# Status_Board.net
KiCad netlist of a schematic drawn in EAGLE
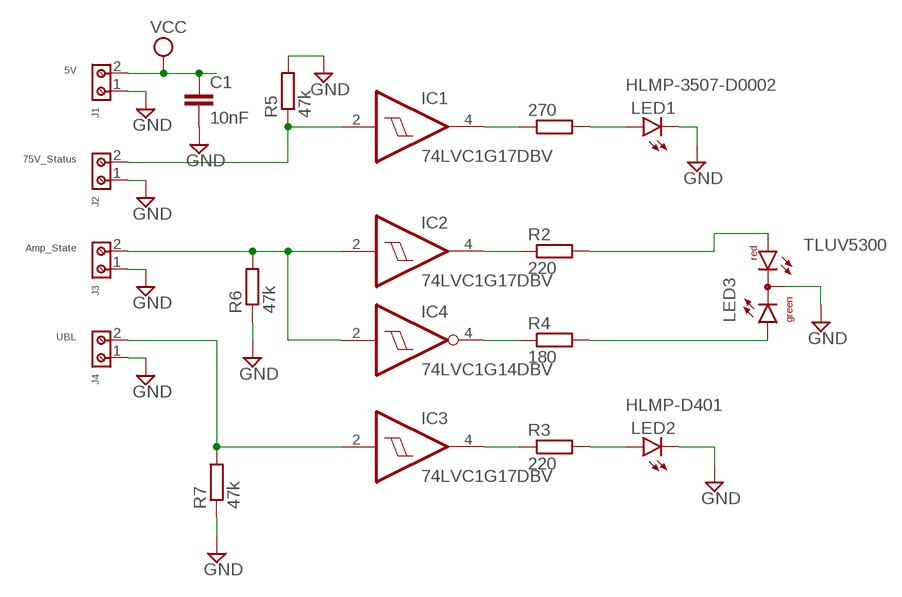
[diagram p0: schematic, sheet 1]

(export (version "E")
  (design (tool "Eeschema 10.0.6"))
  (components
    (comp (ref "270")
      (value "R-EU_R0805")
      (footprint "eagle-import:R0805")
      (libsource (lib "eagle-import") (part "R-EU_R0805"))
    )
    (comp (ref "C1")
      (value "10nF")
      (footprint "eagle-import:C0805")
      (libsource (lib "eagle-import") (part "C-EUC0805"))
    )
    (comp (ref "IC1")
      (value "74LVC1G17DBV")
      (footprint "eagle-import:SOT23-5")
      (libsource (lib "eagle-import") (part "741G17DBVLVC"))
    )
    (comp (ref "IC2")
      (value "74LVC1G17DBV")
      (footprint "eagle-import:SOT23-5")
      (libsource (lib "eagle-import") (part "741G17DBVLVC"))
    )
    (comp (ref "IC3")
      (value "74LVC1G17DBV")
      (footprint "eagle-import:SOT23-5")
      (libsource (lib "eagle-import") (part "741G17DBVLVC"))
    )
    (comp (ref "IC4")
      (value "74LVC1G14DBV")
      (footprint "eagle-import:SOT23-5")
      (libsource (lib "eagle-import") (part "741G14DBVLVC"))
    )
    (comp (ref "J1")
      (value "5V")
      (footprint "eagle-import:691210910002")
      (libsource (lib "eagle-import") (part "691210910002"))
    )
    (comp (ref "J2")
      (value "75V_Status")
      (footprint "eagle-import:691210910002")
      (libsource (lib "eagle-import") (part "691210910002"))
    )
    (comp (ref "J3")
      (value "Amp_State")
      (footprint "eagle-import:691210910002")
      (libsource (lib "eagle-import") (part "691210910002"))
    )
    (comp (ref "J4")
      (value "UBL")
      (footprint "eagle-import:691210910002")
      (libsource (lib "eagle-import") (part "691210910002"))
    )
    (comp (ref "LED1")
      (value "LED5MM")
      (footprint "eagle-import:LED5MM")
      (libsource (lib "eagle-import") (part "LED5MM"))
    )
    (comp (ref "LED2")
      (value "LED5MM")
      (footprint "eagle-import:LED5MM")
      (libsource (lib "eagle-import") (part "LED5MM"))
    )
    (comp (ref "LED3")
      (value "DUOLED-RG-C")
      (footprint "eagle-import:DUOLED-C-5MM")
      (libsource (lib "eagle-import") (part "DUOLED-RG-C"))
    )
    (comp (ref "R2")
      (value "220")
      (footprint "eagle-import:R0805")
      (libsource (lib "eagle-import") (part "R-EU_R0805"))
    )
    (comp (ref "R3")
      (value "220")
      (footprint "eagle-import:R0805")
      (libsource (lib "eagle-import") (part "R-EU_R0805"))
    )
    (comp (ref "R4")
      (value "180")
      (footprint "eagle-import:R0805")
      (libsource (lib "eagle-import") (part "R-EU_R0805"))
    )
    (comp (ref "R5")
      (value "47k")
      (footprint "eagle-import:R0805")
      (libsource (lib "eagle-import") (part "R-EU_R0805"))
    )
    (comp (ref "R6")
      (value "47k")
      (footprint "eagle-import:R0805")
      (libsource (lib "eagle-import") (part "R-EU_R0805"))
    )
    (comp (ref "R7")
      (value "47k")
      (footprint "eagle-import:R0805")
      (libsource (lib "eagle-import") (part "R-EU_R0805"))
    )
  )
  (nets
    (net (code "1") (name "GND") (class "Default")
      (node (ref "C1") (pin "2") (pinfunction "2_2") (pintype "passive"))
      (node (ref "J1") (pin "1") (pinfunction "1_1") (pintype "passive"))
      (node (ref "J2") (pin "1") (pinfunction "1_1") (pintype "passive"))
      (node (ref "J3") (pin "1") (pinfunction "1_1") (pintype "passive"))
      (node (ref "J4") (pin "1") (pinfunction "1_1") (pintype "passive"))
      (node (ref "LED1") (pin "K") (pinfunction "C_K") (pintype "passive"))
      (node (ref "LED2") (pin "K") (pinfunction "C_K") (pintype "passive"))
      (node (ref "LED3") (pin "C") (pinfunction "C_C") (pintype "passive"))
      (node (ref "R5") (pin "2") (pinfunction "2_2") (pintype "passive"))
      (node (ref "R6") (pin "1") (pinfunction "1_1") (pintype "passive"))
      (node (ref "R7") (pin "1") (pinfunction "1_1") (pintype "passive"))
    )
    (net (code "2") (name "Net-(270-Pad2)") (class "Default")
      (node (ref "270") (pin "2") (pinfunction "2_2") (pintype "passive"))
      (node (ref "LED1") (pin "A") (pinfunction "A_A") (pintype "passive"))
    )
    (net (code "3") (name "Net-(IC1A-I)") (class "Default")
      (node (ref "IC1") (pin "2") (pinfunction "I_2") (pintype "input"))
      (node (ref "J2") (pin "2") (pinfunction "2_2") (pintype "passive"))
      (node (ref "R5") (pin "1") (pinfunction "1_1") (pintype "passive"))
    )
    (net (code "4") (name "Net-(IC1A-O)") (class "Default")
      (node (ref "270") (pin "1") (pinfunction "1_1") (pintype "passive"))
      (node (ref "IC1") (pin "4") (pinfunction "O_4") (pintype "output"))
    )
    (net (code "5") (name "Net-(IC2A-I)") (class "Default")
      (node (ref "IC2") (pin "2") (pinfunction "I_2") (pintype "input"))
      (node (ref "IC4") (pin "2") (pinfunction "I_2") (pintype "input"))
      (node (ref "J3") (pin "2") (pinfunction "2_2") (pintype "passive"))
      (node (ref "R6") (pin "2") (pinfunction "2_2") (pintype "passive"))
    )
    (net (code "6") (name "Net-(IC2A-O)") (class "Default")
      (node (ref "IC2") (pin "4") (pinfunction "O_4") (pintype "output"))
      (node (ref "R2") (pin "1") (pinfunction "1_1") (pintype "passive"))
    )
    (net (code "7") (name "Net-(IC3A-I)") (class "Default")
      (node (ref "IC3") (pin "2") (pinfunction "I_2") (pintype "input"))
      (node (ref "J4") (pin "2") (pinfunction "2_2") (pintype "passive"))
      (node (ref "R7") (pin "2") (pinfunction "2_2") (pintype "passive"))
    )
    (net (code "8") (name "Net-(IC3A-O)") (class "Default")
      (node (ref "IC3") (pin "4") (pinfunction "O_4") (pintype "output"))
      (node (ref "R3") (pin "1") (pinfunction "1_1") (pintype "passive"))
    )
    (net (code "9") (name "Net-(IC4A-O)") (class "Default")
      (node (ref "IC4") (pin "4") (pinfunction "O_4") (pintype "output"))
      (node (ref "R4") (pin "1") (pinfunction "1_1") (pintype "passive"))
    )
    (net (code "10") (name "Net-(LED2-PadA)") (class "Default")
      (node (ref "LED2") (pin "A") (pinfunction "A_A") (pintype "passive"))
      (node (ref "R3") (pin "2") (pinfunction "2_2") (pintype "passive"))
    )
    (net (code "11") (name "Net-(LED3-AG)") (class "Default")
      (node (ref "LED3") (pin "AX") (pinfunction "AG_AX") (pintype "passive"))
      (node (ref "R4") (pin "2") (pinfunction "2_2") (pintype "passive"))
    )
    (net (code "12") (name "Net-(LED3-PadAR)") (class "Default")
      (node (ref "LED3") (pin "AR") (pinfunction "AR_AR") (pintype "passive"))
      (node (ref "R2") (pin "2") (pinfunction "2_2") (pintype "passive"))
    )
    (net (code "13") (name "VCC") (class "Default")
      (node (ref "C1") (pin "1") (pinfunction "1_1") (pintype "passive"))
      (node (ref "J1") (pin "2") (pinfunction "2_2") (pintype "passive"))
    )
  )
)
